# openSX70_ALADDIN_V39_20180122.net
KiCad netlist of a schematic drawn in EAGLE
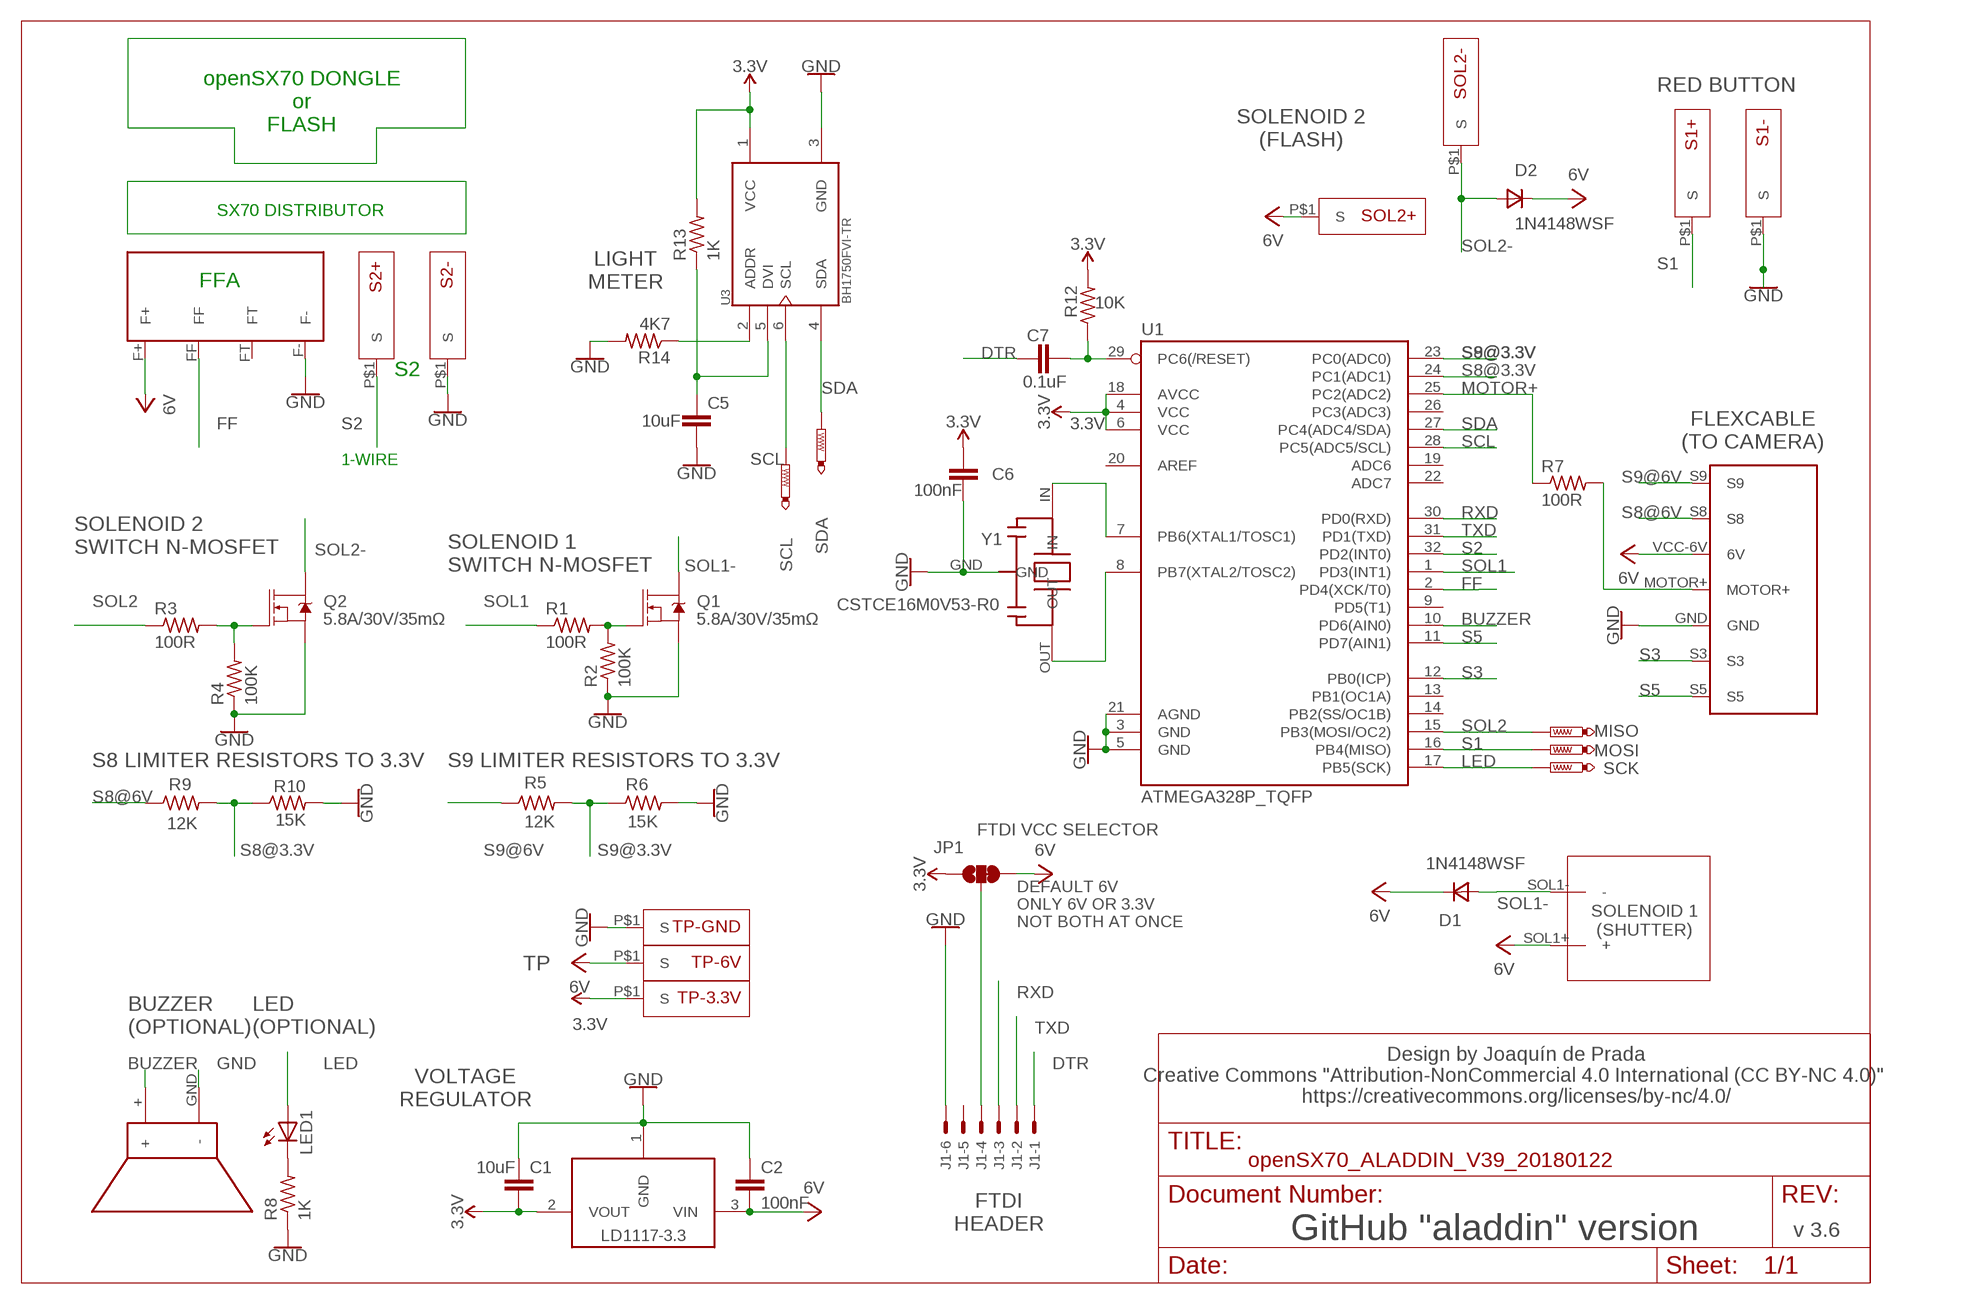
[diagram p0: schematic, sheet 1]

(export (version "E")
  (design (tool "Eeschema 10.0.6"))
  (components
    (comp (ref "BUZZ1")
      (value "CSET8-5G")
      (footprint "eagle-import:CSET8-5G_PACKAGE")
      (libsource (lib "eagle-import") (part "CSET8-5G"))
    )
    (comp (ref "C1")
      (value "10uF")
      (footprint "eagle-import:0603")
      (libsource (lib "eagle-import") (part "10UF-0603-6.3V-20%"))
    )
    (comp (ref "C2")
      (value "100nF")
      (footprint "eagle-import:C0603K")
      (libsource (lib "eagle-import") (part "C-EUC0603K"))
    )
    (comp (ref "C5")
      (value "10uF")
      (footprint "eagle-import:0603")
      (libsource (lib "eagle-import") (part "10UF-0603-6.3V-20%"))
    )
    (comp (ref "C6")
      (value "100nF")
      (footprint "eagle-import:C0603")
      (libsource (lib "eagle-import") (part "C-EUC0603"))
    )
    (comp (ref "C7")
      (value "0.1uF")
      (footprint "eagle-import:0603")
      (libsource (lib "eagle-import") (part "0.1UF-0603-25V-(+80/-20%)"))
    )
    (comp (ref "D1")
      (value "1N4148WSF")
      (footprint "eagle-import:SOD323")
      (fields (field (name "MPN") "CDSOD323-T05C"))
      (libsource (lib "eagle-import") (part "DSOD323"))
    )
    (comp (ref "D2")
      (value "1N4148WSF")
      (footprint "eagle-import:SOD323")
      (fields (field (name "MPN") "CDSOD323-T05C"))
      (libsource (lib "eagle-import") (part "DSOD323"))
    )
    (comp (ref "J1")
      (value "GND")
      (footprint "eagle-import:XF2L-0625-1")
      (fields (field (name "MF") "OMRON COMPONENTS USA") (field (name "MPN") "XF2L-0625-1"))
      (libsource (lib "eagle-import") (part "XF2-06?25-1L"))
    )
    (comp (ref "JP1")
      (value "FTDI VCC SELECTOR")
      (footprint "eagle-import:SMT-JUMPER_3_1-NC_TRACE_SILK")
      (libsource (lib "eagle-import") (part "JUMPER-SMT_3_1-NC_TRACE_SILK"))
    )
    (comp (ref "LD11173.3V")
      (value "LD1117 3.3V")
      (footprint "eagle-import:SOT223")
      (fields (field (name "MF") "Advanced Monolithic Systems") (field (name "MP") "AMS1117-5.0"))
      (libsource (lib "eagle-import") (part "LD1117-3.3"))
    )
    (comp (ref "LED1")
      (value "LEDCHIPLED_0805")
      (footprint "eagle-import:CHIPLED_0805")
      (libsource (lib "eagle-import") (part "LEDCHIPLED_0805"))
    )
    (comp (ref "MISO")
      (value "PTR1TP08R")
      (footprint "eagle-import:TP08R")
      (libsource (lib "eagle-import") (part "PTR1TP08R"))
    )
    (comp (ref "MOSI")
      (value "PTR1TP08R")
      (footprint "eagle-import:TP08R")
      (libsource (lib "eagle-import") (part "PTR1TP08R"))
    )
    (comp (ref "Q1")
      (value "5.8A/30V/35mΩ")
      (footprint "eagle-import:SOT23-3")
      (libsource (lib "eagle-import") (part "MOSFET-NCH-AO3404A"))
    )
    (comp (ref "Q2")
      (value "5.8A/30V/35mΩ")
      (footprint "eagle-import:SOT23-3")
      (libsource (lib "eagle-import") (part "MOSFET-NCH-AO3404A"))
    )
    (comp (ref "R1")
      (value "100R")
      (footprint "eagle-import:R0603")
      (libsource (lib "eagle-import") (part "R-US_R0603"))
    )
    (comp (ref "R2")
      (value "100K")
      (footprint "eagle-import:R0603")
      (libsource (lib "eagle-import") (part "R-US_R0603"))
    )
    (comp (ref "R3")
      (value "100R")
      (footprint "eagle-import:R0603")
      (libsource (lib "eagle-import") (part "R-US_R0603"))
    )
    (comp (ref "R4")
      (value "100K")
      (footprint "eagle-import:R0603")
      (libsource (lib "eagle-import") (part "R-US_R0603"))
    )
    (comp (ref "R5")
      (value "12K")
      (footprint "eagle-import:R0603")
      (libsource (lib "eagle-import") (part "R-US_R0603"))
    )
    (comp (ref "R6")
      (value "15K")
      (footprint "eagle-import:R0603")
      (libsource (lib "eagle-import") (part "R-US_R0603"))
    )
    (comp (ref "R7")
      (value "100R")
      (footprint "eagle-import:R0603")
      (libsource (lib "eagle-import") (part "R-US_R0603"))
    )
    (comp (ref "R8")
      (value "1K")
      (footprint "eagle-import:R0603")
      (libsource (lib "eagle-import") (part "R-US_R0603"))
    )
    (comp (ref "R9")
      (value "12K")
      (footprint "eagle-import:R0603")
      (libsource (lib "eagle-import") (part "R-US_R0603"))
    )
    (comp (ref "R10")
      (value "15K")
      (footprint "eagle-import:R0603")
      (libsource (lib "eagle-import") (part "R-US_R0603"))
    )
    (comp (ref "R12")
      (value "10K")
      (footprint "eagle-import:R0603")
      (libsource (lib "eagle-import") (part "R-US_R0603"))
    )
    (comp (ref "R13")
      (value "1K")
      (footprint "eagle-import:R0603")
      (libsource (lib "eagle-import") (part "R-US_R0603"))
    )
    (comp (ref "R14")
      (value "4K7")
      (footprint "eagle-import:R0603")
      (libsource (lib "eagle-import") (part "R-US_R0603"))
    )
    (comp (ref "S1+")
      (value "SX70-S-PAD-NEW")
      (footprint "eagle-import:SX70-S-PAD2")
      (libsource (lib "eagle-import") (part "SX70-S-PAD-NEW"))
    )
    (comp (ref "S1-")
      (value "SX70-S-PAD-NEW")
      (footprint "eagle-import:SX70-S-PAD2")
      (libsource (lib "eagle-import") (part "SX70-S-PAD-NEW"))
    )
    (comp (ref "S2+")
      (value "SX70-S-PAD-NEW")
      (footprint "eagle-import:SX70-S-PAD2")
      (libsource (lib "eagle-import") (part "SX70-S-PAD-NEW"))
    )
    (comp (ref "S2-")
      (value "SX70-S-PAD-NEW")
      (footprint "eagle-import:SX70-S-PAD2")
      (libsource (lib "eagle-import") (part "SX70-S-PAD-NEW"))
    )
    (comp (ref "SCK")
      (value "PTR1TP08R")
      (footprint "eagle-import:TP08R")
      (libsource (lib "eagle-import") (part "PTR1TP08R"))
    )
    (comp (ref "SCL")
      (value "PTR1TP08R")
      (footprint "eagle-import:TP08R")
      (libsource (lib "eagle-import") (part "PTR1TP08R"))
    )
    (comp (ref "SDA")
      (value "PTR1TP08R")
      (footprint "eagle-import:TP08R")
      (libsource (lib "eagle-import") (part "PTR1TP08R"))
    )
    (comp (ref "SOL1")
      (value "SX70-SOLENOID1-2PADS")
      (footprint "eagle-import:SX70-SOLENOID1-2")
      (libsource (lib "eagle-import") (part "SX70-SOLENOID1-2PADS"))
    )
    (comp (ref "SOL2+")
      (value "SX70-S-PAD-NEW")
      (footprint "eagle-import:SX70-S-PAD2")
      (libsource (lib "eagle-import") (part "SX70-S-PAD-NEW"))
    )
    (comp (ref "SOL2-")
      (value "SX70-S-PAD-NEW")
      (footprint "eagle-import:SX70-S-PAD2")
      (libsource (lib "eagle-import") (part "SX70-S-PAD-NEW"))
    )
    (comp (ref "TP-3.3V")
      (value "SX70-S-PAD-NEW")
      (footprint "eagle-import:SX70-S-PAD2")
      (libsource (lib "eagle-import") (part "SX70-S-PAD-NEW"))
    )
    (comp (ref "TP-6V")
      (value "SX70-S-PAD-NEW")
      (footprint "eagle-import:SX70-S-PAD2")
      (libsource (lib "eagle-import") (part "SX70-S-PAD-NEW"))
    )
    (comp (ref "TP-GND")
      (value "SX70-S-PAD-NEW")
      (footprint "eagle-import:SX70-S-PAD2")
      (libsource (lib "eagle-import") (part "SX70-S-PAD-NEW"))
    )
    (comp (ref "U$1")
      (value "SX70-7-PAD")
      (footprint "eagle-import:SX70-7-PAD")
      (libsource (lib "eagle-import") (part "SX70-7-PAD"))
    )
    (comp (ref "U$2")
      (value "FFA")
      (footprint "eagle-import:FFA-PAD-PACKAGE")
      (libsource (lib "eagle-import") (part "SX70-FFA-PAD"))
    )
    (comp (ref "U1")
      (value "ATMEGA328P_TQFP")
      (footprint "eagle-import:TQFP32-08")
      (libsource (lib "eagle-import") (part "ATMEGA328P_TQFP"))
    )
    (comp (ref "U3")
      (value "BH1750FVI-TR")
      (footprint "eagle-import:SOTFL50P300X75-6N")
      (fields (field (name "MF") "Rohm"))
      (libsource (lib "eagle-import") (part "BH1750FVI-TR"))
    )
    (comp (ref "Y1")
      (value "CSTCE16M0V53-R0")
      (footprint "eagle-import:CFP95P160X100-3N")
      (fields (field (name "MF") "Murata"))
      (libsource (lib "eagle-import") (part "CSTCE16M0V53-R0"))
    )
  )
  (nets
    (net (code "1") (name "/BUZZER") (class "Default")
      (node (ref "BUZZ1") (pin "+") (pinfunction "+_+") (pintype "bidirectional"))
      (node (ref "U1") (pin "10") (pinfunction "PD6(AIN0)_10") (pintype "bidirectional"))
    )
    (net (code "2") (name "/DTR") (class "Default")
      (node (ref "C7") (pin "1") (pinfunction "1_1") (pintype "passive"))
      (node (ref "J1") (pin "1") (pinfunction "MS_1") (pintype "passive"))
    )
    (net (code "3") (name "/FF") (class "Default")
      (node (ref "U$2") (pin "FF") (pinfunction "FF_FF") (pintype "bidirectional"))
      (node (ref "U1") (pin "2") (pinfunction "PD4(XCK/T0)_2") (pintype "bidirectional"))
    )
    (net (code "4") (name "/LED") (class "Default")
      (node (ref "LED1") (pin "A") (pinfunction "A_A") (pintype "passive"))
      (node (ref "SCK") (pin "TP") (pinfunction "TP_TP") (pintype "input"))
      (node (ref "U1") (pin "17") (pinfunction "PB5(SCK)_17") (pintype "bidirectional"))
    )
    (net (code "5") (name "/MOTOR+") (class "Default")
      (node (ref "R7") (pin "1") (pinfunction "1_1") (pintype "passive"))
      (node (ref "U1") (pin "25") (pinfunction "PC2(ADC2)_25") (pintype "bidirectional"))
    )
    (net (code "6") (name "/RXD") (class "Default")
      (node (ref "J1") (pin "3") (pinfunction "MS_3") (pintype "passive"))
      (node (ref "U1") (pin "30") (pinfunction "PD0(RXD)_30") (pintype "bidirectional"))
    )
    (net (code "7") (name "/S1") (class "Default")
      (node (ref "MOSI") (pin "TP") (pinfunction "TP_TP") (pintype "input"))
      (node (ref "S1+") (pin "P$1") (pinfunction "S_P$1") (pintype "bidirectional"))
      (node (ref "U1") (pin "16") (pinfunction "PB4(MISO)_16") (pintype "bidirectional"))
    )
    (net (code "8") (name "/S2") (class "Default")
      (node (ref "S2+") (pin "P$1") (pinfunction "S_P$1") (pintype "bidirectional"))
      (node (ref "U1") (pin "32") (pinfunction "PD2(INT0)_32") (pintype "bidirectional"))
    )
    (net (code "9") (name "/S3") (class "Default")
      (node (ref "U$1") (pin "S3") (pinfunction "S3_S3") (pintype "bidirectional"))
      (node (ref "U1") (pin "12") (pinfunction "PB0(ICP)_12") (pintype "bidirectional"))
    )
    (net (code "10") (name "/S5") (class "Default")
      (node (ref "U$1") (pin "S5") (pinfunction "S5_S5") (pintype "bidirectional"))
      (node (ref "U1") (pin "11") (pinfunction "PD7(AIN1)_11") (pintype "bidirectional"))
    )
    (net (code "11") (name "/S8@3.3V") (class "Default")
      (node (ref "R10") (pin "1") (pinfunction "1_1") (pintype "passive"))
      (node (ref "R9") (pin "2") (pinfunction "2_2") (pintype "passive"))
      (node (ref "U1") (pin "24") (pinfunction "PC1(ADC1)_24") (pintype "bidirectional"))
    )
    (net (code "12") (name "/S8@6V") (class "Default")
      (node (ref "R9") (pin "1") (pinfunction "1_1") (pintype "passive"))
      (node (ref "U$1") (pin "S8") (pinfunction "S8_S8") (pintype "bidirectional"))
    )
    (net (code "13") (name "/S9@3.3V") (class "Default")
      (node (ref "R5") (pin "2") (pinfunction "2_2") (pintype "passive"))
      (node (ref "R6") (pin "1") (pinfunction "1_1") (pintype "passive"))
      (node (ref "U1") (pin "23") (pinfunction "PC0(ADC0)_23") (pintype "bidirectional"))
    )
    (net (code "14") (name "/S9@6V") (class "Default")
      (node (ref "R5") (pin "1") (pinfunction "1_1") (pintype "passive"))
      (node (ref "U$1") (pin "S9") (pinfunction "S9_S9") (pintype "bidirectional"))
    )
    (net (code "15") (name "/SCL") (class "Default")
      (node (ref "SCL") (pin "TP") (pinfunction "TP_TP") (pintype "input"))
      (node (ref "U1") (pin "28") (pinfunction "PC5(ADC5/SCL)_28") (pintype "bidirectional"))
      (node (ref "U3") (pin "6") (pinfunction "SCL_6") (pintype "input"))
    )
    (net (code "16") (name "/SDA") (class "Default")
      (node (ref "SDA") (pin "TP") (pinfunction "TP_TP") (pintype "input"))
      (node (ref "U1") (pin "27") (pinfunction "PC4(ADC4/SDA)_27") (pintype "bidirectional"))
      (node (ref "U3") (pin "4") (pinfunction "SDA_4") (pintype "bidirectional"))
    )
    (net (code "17") (name "/SOL1") (class "Default")
      (node (ref "R1") (pin "1") (pinfunction "1_1") (pintype "passive"))
      (node (ref "U1") (pin "1") (pinfunction "PD3(INT1)_1") (pintype "bidirectional"))
    )
    (net (code "18") (name "/SOL1-") (class "Default")
      (node (ref "D1") (pin "2") (pinfunction "A_2") (pintype "passive"))
      (node (ref "Q1") (pin "3") (pinfunction "D_3") (pintype "bidirectional"))
      (node (ref "SOL1") (pin "SOL1-") (pinfunction "-_SOL1-") (pintype "bidirectional"))
    )
    (net (code "19") (name "/SOL2") (class "Default")
      (node (ref "MISO") (pin "TP") (pinfunction "TP_TP") (pintype "input"))
      (node (ref "R3") (pin "1") (pinfunction "1_1") (pintype "passive"))
      (node (ref "U1") (pin "15") (pinfunction "PB3(MOSI/OC2)_15") (pintype "bidirectional"))
    )
    (net (code "20") (name "/SOL2-") (class "Default")
      (node (ref "D2") (pin "2") (pinfunction "A_2") (pintype "passive"))
      (node (ref "Q2") (pin "3") (pinfunction "D_3") (pintype "bidirectional"))
      (node (ref "SOL2-") (pin "P$1") (pinfunction "S_P$1") (pintype "bidirectional"))
    )
    (net (code "21") (name "/TXD") (class "Default")
      (node (ref "J1") (pin "2") (pinfunction "MS_2") (pintype "passive"))
      (node (ref "U1") (pin "31") (pinfunction "PD1(TXD)_31") (pintype "bidirectional"))
    )
    (net (code "22") (name "3.3V") (class "Default")
      (node (ref "C1") (pin "2") (pinfunction "2_2") (pintype "passive"))
      (node (ref "C6") (pin "1") (pinfunction "1_1") (pintype "passive"))
      (node (ref "JP1") (pin "1") (pinfunction "1_1") (pintype "passive"))
      (node (ref "LD11173.3V") (pin "2") (pinfunction "VOUT_2") (pintype "bidirectional"))
      (node (ref "R12") (pin "2") (pinfunction "2_2") (pintype "passive"))
      (node (ref "R13") (pin "2") (pinfunction "2_2") (pintype "passive"))
      (node (ref "TP-3.3V") (pin "P$1") (pinfunction "S_P$1") (pintype "bidirectional"))
      (node (ref "U1") (pin "18") (pinfunction "AVCC_18") (pintype "bidirectional"))
      (node (ref "U1") (pin "4") (pinfunction "VCC_4") (pintype "bidirectional"))
      (node (ref "U1") (pin "6") (pinfunction "VCC_6") (pintype "bidirectional"))
      (node (ref "U3") (pin "1") (pinfunction "VCC_1") (pintype "power_in"))
    )
    (net (code "23") (name "6V") (class "Default")
      (node (ref "C2") (pin "2") (pinfunction "2_2") (pintype "passive"))
      (node (ref "D1") (pin "1") (pinfunction "C_1") (pintype "passive"))
      (node (ref "D2") (pin "1") (pinfunction "C_1") (pintype "passive"))
      (node (ref "JP1") (pin "3") (pinfunction "3_3") (pintype "passive"))
      (node (ref "LD11173.3V") (pin "3") (pinfunction "VIN_3") (pintype "bidirectional"))
      (node (ref "SOL1") (pin "SOL1+") (pinfunction "+_SOL1+") (pintype "bidirectional"))
      (node (ref "SOL2+") (pin "P$1") (pinfunction "S_P$1") (pintype "bidirectional"))
      (node (ref "TP-6V") (pin "P$1") (pinfunction "S_P$1") (pintype "bidirectional"))
      (node (ref "U$1") (pin "VCC-6V") (pinfunction "6V_VCC-6V") (pintype "bidirectional"))
      (node (ref "U$2") (pin "F+") (pinfunction "F+_F+") (pintype "bidirectional"))
    )
    (net (code "24") (name "GND") (class "Default")
      (node (ref "BUZZ1") (pin "GND") (pinfunction "-_GND") (pintype "bidirectional"))
      (node (ref "C1") (pin "1") (pinfunction "1_1") (pintype "passive"))
      (node (ref "C2") (pin "1") (pinfunction "1_1") (pintype "passive"))
      (node (ref "C5") (pin "2") (pinfunction "2_2") (pintype "passive"))
      (node (ref "C6") (pin "2") (pinfunction "2_2") (pintype "passive"))
      (node (ref "J1") (pin "6") (pinfunction "MS_6") (pintype "passive"))
      (node (ref "LD11173.3V") (pin "1") (pinfunction "GND_1") (pintype "bidirectional"))
      (node (ref "Q1") (pin "2") (pinfunction "S_2") (pintype "bidirectional"))
      (node (ref "Q2") (pin "2") (pinfunction "S_2") (pintype "bidirectional"))
      (node (ref "R10") (pin "2") (pinfunction "2_2") (pintype "passive"))
      (node (ref "R14") (pin "2") (pinfunction "2_2") (pintype "passive"))
      (node (ref "R2") (pin "1") (pinfunction "1_1") (pintype "passive"))
      (node (ref "R4") (pin "1") (pinfunction "1_1") (pintype "passive"))
      (node (ref "R6") (pin "2") (pinfunction "2_2") (pintype "passive"))
      (node (ref "R8") (pin "1") (pinfunction "1_1") (pintype "passive"))
      (node (ref "S1-") (pin "P$1") (pinfunction "S_P$1") (pintype "bidirectional"))
      (node (ref "S2-") (pin "P$1") (pinfunction "S_P$1") (pintype "bidirectional"))
      (node (ref "TP-GND") (pin "P$1") (pinfunction "S_P$1") (pintype "bidirectional"))
      (node (ref "U$1") (pin "GND") (pinfunction "GND_GND") (pintype "bidirectional"))
      (node (ref "U$2") (pin "F-") (pinfunction "F-_F-") (pintype "bidirectional"))
      (node (ref "U1") (pin "21") (pinfunction "AGND_21") (pintype "bidirectional"))
      (node (ref "U1") (pin "3") (pinfunction "GND_3") (pintype "bidirectional"))
      (node (ref "U1") (pin "5") (pinfunction "GND_5") (pintype "bidirectional"))
      (node (ref "U3") (pin "3") (pinfunction "GND_3") (pintype "power_in"))
      (node (ref "Y1") (pin "GND") (pinfunction "GND_GND") (pintype "passive"))
    )
    (net (code "25") (name "Net-(LED1-PadC)") (class "Default")
      (node (ref "LED1") (pin "C") (pinfunction "C_C") (pintype "passive"))
      (node (ref "R8") (pin "2") (pinfunction "2_2") (pintype "passive"))
    )
    (net (code "26") (name "Net-(Q1-G)") (class "Default")
      (node (ref "Q1") (pin "1") (pinfunction "G_1") (pintype "bidirectional"))
      (node (ref "R1") (pin "2") (pinfunction "2_2") (pintype "passive"))
      (node (ref "R2") (pin "2") (pinfunction "2_2") (pintype "passive"))
    )
    (net (code "27") (name "Net-(Q2-G)") (class "Default")
      (node (ref "Q2") (pin "1") (pinfunction "G_1") (pintype "bidirectional"))
      (node (ref "R3") (pin "2") (pinfunction "2_2") (pintype "passive"))
      (node (ref "R4") (pin "2") (pinfunction "2_2") (pintype "passive"))
    )
    (net (code "28") (name "Net-(R7-Pad2)") (class "Default")
      (node (ref "R7") (pin "2") (pinfunction "2_2") (pintype "passive"))
      (node (ref "U$1") (pin "MOTOR+") (pinfunction "MOTOR+_MOTOR+") (pintype "bidirectional"))
    )
    (net (code "29") (name "Net-(U1-PB6(XTAL1{slash}TOSC1))") (class "Default")
      (node (ref "U1") (pin "7") (pinfunction "PB6(XTAL1/TOSC1)_7") (pintype "bidirectional"))
      (node (ref "Y1") (pin "IN") (pinfunction "IN_IN") (pintype "input"))
    )
    (net (code "30") (name "Net-(U1-PB7(XTAL2{slash}TOSC2))") (class "Default")
      (node (ref "U1") (pin "8") (pinfunction "PB7(XTAL2/TOSC2)_8") (pintype "bidirectional"))
      (node (ref "Y1") (pin "OUT") (pinfunction "OUT_OUT") (pintype "output"))
    )
    (net (code "31") (name "Net-(U1-PC6({slash}RESET))") (class "Default")
      (node (ref "C7") (pin "2") (pinfunction "2_2") (pintype "passive"))
      (node (ref "R12") (pin "1") (pinfunction "1_1") (pintype "passive"))
      (node (ref "U1") (pin "29") (pinfunction "PC6(/RESET)_29") (pintype "bidirectional"))
    )
    (net (code "32") (name "Net-(U3-ADDR)") (class "Default")
      (node (ref "R14") (pin "1") (pinfunction "1_1") (pintype "passive"))
      (node (ref "U3") (pin "2") (pinfunction "ADDR_2") (pintype "input"))
    )
    (net (code "33") (name "Net-(U3-DVI)") (class "Default")
      (node (ref "C5") (pin "1") (pinfunction "1_1") (pintype "passive"))
      (node (ref "R13") (pin "1") (pinfunction "1_1") (pintype "passive"))
      (node (ref "U3") (pin "5") (pinfunction "DVI_5") (pintype "input"))
    )
    (net (code "34") (name "unconnected-(J1D-MS-Pad4)") (class "Default")
      (node (ref "J1") (pin "4") (pinfunction "MS_4") (pintype "passive"))
    )
    (net (code "35") (name "unconnected-(J1E-MS-Pad5)") (class "Default")
      (node (ref "J1") (pin "5") (pinfunction "MS_5") (pintype "passive"))
    )
    (net (code "36") (name "unconnected-(JP1-Pad2)") (class "Default")
      (node (ref "JP1") (pin "2") (pinfunction "2_2") (pintype "passive"))
    )
    (net (code "37") (name "unconnected-(U$2-PadFT)") (class "Default")
      (node (ref "U$2") (pin "FT") (pinfunction "FT_FT") (pintype "bidirectional"))
    )
    (net (code "38") (name "unconnected-(U1-ADC6-Pad19)") (class "Default")
      (node (ref "U1") (pin "19") (pinfunction "ADC6_19") (pintype "bidirectional"))
    )
    (net (code "39") (name "unconnected-(U1-ADC7-Pad22)") (class "Default")
      (node (ref "U1") (pin "22") (pinfunction "ADC7_22") (pintype "bidirectional"))
    )
    (net (code "40") (name "unconnected-(U1-AREF-Pad20)") (class "Default")
      (node (ref "U1") (pin "20") (pinfunction "AREF_20") (pintype "bidirectional"))
    )
    (net (code "41") (name "unconnected-(U1-PB1(OC1A)-Pad13)") (class "Default")
      (node (ref "U1") (pin "13") (pinfunction "PB1(OC1A)_13") (pintype "bidirectional"))
    )
    (net (code "42") (name "unconnected-(U1-PB2(SS{slash}OC1B)-Pad14)") (class "Default")
      (node (ref "U1") (pin "14") (pinfunction "PB2(SS/OC1B)_14") (pintype "bidirectional"))
    )
    (net (code "43") (name "unconnected-(U1-PC3(ADC3)-Pad26)") (class "Default")
      (node (ref "U1") (pin "26") (pinfunction "PC3(ADC3)_26") (pintype "bidirectional"))
    )
    (net (code "44") (name "unconnected-(U1-PD5(T1)-Pad9)") (class "Default")
      (node (ref "U1") (pin "9") (pinfunction "PD5(T1)_9") (pintype "bidirectional"))
    )
  )
)
